# Top.net
KiCad netlist of a schematic drawn in Altium Designer
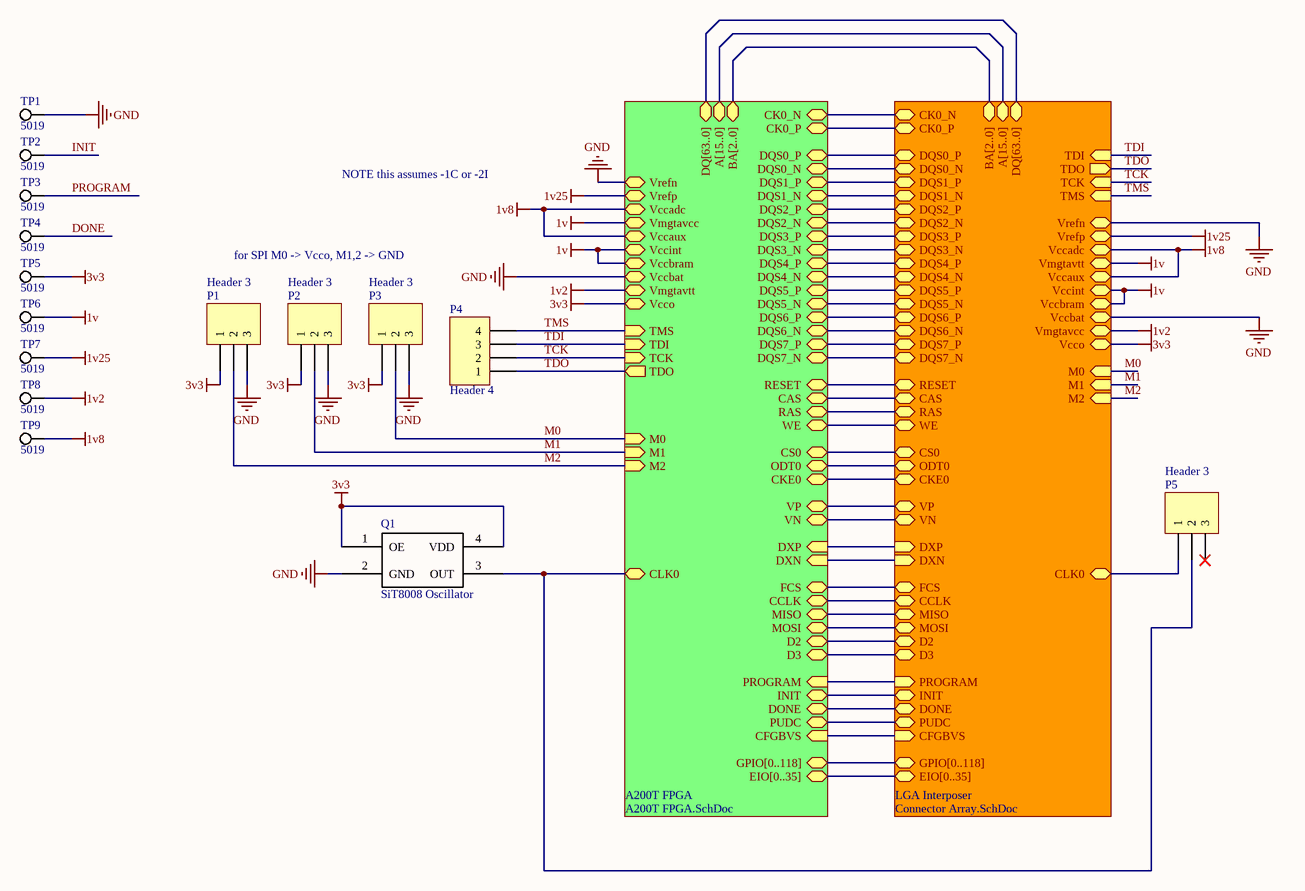
[diagram p0: Top.SchDoc]

(export (version "E")
  (design (tool "Eeschema 10.0.6"))
  (components
    (comp (ref "P1")
      (value "Header 3")
      (footprint "HDR1X3")
      (description "Header, 3-Pin")
      (fields (field (name "PUBLISHER") "Altium Limited"))
      (libsource (lib "Miscellaneous Connectors") (part "Header 3"))
    )
    (comp (ref "P2")
      (value "Header 3")
      (footprint "HDR1X3")
      (description "Header, 3-Pin")
      (fields (field (name "PUBLISHER") "Altium Limited"))
      (libsource (lib "Miscellaneous Connectors") (part "Header 3"))
    )
    (comp (ref "P3")
      (value "Header 3")
      (footprint "HDR1X3")
      (description "Header, 3-Pin")
      (fields (field (name "PUBLISHER") "Altium Limited"))
      (libsource (lib "Miscellaneous Connectors") (part "Header 3"))
    )
    (comp (ref "P4")
      (value "Header 4")
      (footprint "HDR1X4")
      (description "Header, 4-Pin")
      (fields (field (name "PUBLISHER") "Altium Limited"))
      (libsource (lib "Miscellaneous Connectors") (part "Header 4"))
    )
    (comp (ref "P5")
      (value "Header 3")
      (footprint "HDR1X3")
      (description "Header, 3-Pin")
      (fields (field (name "PUBLISHER") "Altium Limited"))
      (libsource (lib "Miscellaneous Connectors") (part "Header 3"))
    )
    (comp (ref "Q1")
      (value "SiT8008 Oscillator")
      (footprint "SiT8008 2.5x2")
      (libsource (lib "2020-09-26_17-27-19") (part "SiT8008 Oscillator"))
    )
    (comp (ref "TP1")
      (value "5019")
      (footprint "KSTN-5019_V")
      (description "Test Point, 1 Position SMD, RoHS, Tape and Reel")
      (libsource (lib "Altium Content Vault") (part "TESTPOINT_WHITE"))
    )
    (comp (ref "TP2")
      (value "5019")
      (footprint "KSTN-5019_V")
      (description "Test Point, 1 Position SMD, RoHS, Tape and Reel")
      (libsource (lib "Altium Content Vault") (part "TESTPOINT_WHITE"))
    )
    (comp (ref "TP3")
      (value "5019")
      (footprint "KSTN-5019_V")
      (description "Test Point, 1 Position SMD, RoHS, Tape and Reel")
      (libsource (lib "Altium Content Vault") (part "TESTPOINT_WHITE"))
    )
    (comp (ref "TP4")
      (value "5019")
      (footprint "KSTN-5019_V")
      (description "Test Point, 1 Position SMD, RoHS, Tape and Reel")
      (libsource (lib "Altium Content Vault") (part "TESTPOINT_WHITE"))
    )
    (comp (ref "TP5")
      (value "5019")
      (footprint "KSTN-5019_V")
      (description "Test Point, 1 Position SMD, RoHS, Tape and Reel")
      (libsource (lib "Altium Content Vault") (part "TESTPOINT_WHITE"))
    )
    (comp (ref "TP6")
      (value "5019")
      (footprint "KSTN-5019_V")
      (description "Test Point, 1 Position SMD, RoHS, Tape and Reel")
      (libsource (lib "Altium Content Vault") (part "TESTPOINT_WHITE"))
    )
    (comp (ref "TP7")
      (value "5019")
      (footprint "KSTN-5019_V")
      (description "Test Point, 1 Position SMD, RoHS, Tape and Reel")
      (libsource (lib "Altium Content Vault") (part "TESTPOINT_WHITE"))
    )
    (comp (ref "TP8")
      (value "5019")
      (footprint "KSTN-5019_V")
      (description "Test Point, 1 Position SMD, RoHS, Tape and Reel")
      (libsource (lib "Altium Content Vault") (part "TESTPOINT_WHITE"))
    )
    (comp (ref "TP9")
      (value "5019")
      (footprint "KSTN-5019_V")
      (description "Test Point, 1 Position SMD, RoHS, Tape and Reel")
      (libsource (lib "Altium Content Vault") (part "TESTPOINT_WHITE"))
    )
  )
  (nets
    (net (code "9") (name "/CLK0") (class "Default")
      (node (ref "P5") (pin "1") (pinfunction "1_1") (pintype "passive"))
    )
    (net (code "10") (name "/CLK0_1") (class "Default")
      (node (ref "P5") (pin "2") (pinfunction "2_2") (pintype "passive"))
      (node (ref "Q1") (pin "3") (pinfunction "OUT_3") (pintype "passive"))
    )
    (net (code "14") (name "/DONE") (class "Default")
      (node (ref "TP4") (pin "1") (pinfunction "1_1") (pintype "passive"))
    )
    (net (code "38") (name "/INIT") (class "Default")
      (node (ref "TP2") (pin "1") (pinfunction "1_1") (pintype "passive"))
    )
    (net (code "40") (name "/M0") (class "Default")
      (node (ref "P3") (pin "2") (pinfunction "2_2") (pintype "passive"))
    )
    (net (code "41") (name "/M1") (class "Default")
      (node (ref "P2") (pin "2") (pinfunction "2_2") (pintype "passive"))
    )
    (net (code "42") (name "/M2") (class "Default")
      (node (ref "P1") (pin "2") (pinfunction "2_2") (pintype "passive"))
    )
    (net (code "46") (name "/PROGRAM") (class "Default")
      (node (ref "TP3") (pin "1") (pinfunction "1_1") (pintype "passive"))
    )
    (net (code "51") (name "/TCK") (class "Default")
      (node (ref "P4") (pin "2") (pinfunction "2_2") (pintype "passive"))
    )
    (net (code "52") (name "/TDI") (class "Default")
      (node (ref "P4") (pin "3") (pinfunction "3_3") (pintype "passive"))
    )
    (net (code "53") (name "/TDO") (class "Default")
      (node (ref "P4") (pin "1") (pinfunction "1_1") (pintype "passive"))
    )
    (net (code "54") (name "/TMS") (class "Default")
      (node (ref "P4") (pin "4") (pinfunction "4_4") (pintype "passive"))
    )
    (net (code "58") (name "1v") (class "Default")
      (node (ref "TP6") (pin "1") (pinfunction "1_1") (pintype "passive"))
    )
    (net (code "59") (name "1v2") (class "Default")
      (node (ref "TP8") (pin "1") (pinfunction "1_1") (pintype "passive"))
    )
    (net (code "60") (name "1v8") (class "Default")
      (node (ref "TP9") (pin "1") (pinfunction "1_1") (pintype "passive"))
    )
    (net (code "61") (name "1v25") (class "Default")
      (node (ref "TP7") (pin "1") (pinfunction "1_1") (pintype "passive"))
    )
    (net (code "62") (name "3v3") (class "Default")
      (node (ref "P1") (pin "1") (pinfunction "1_1") (pintype "passive"))
      (node (ref "P2") (pin "1") (pinfunction "1_1") (pintype "passive"))
      (node (ref "P3") (pin "1") (pinfunction "1_1") (pintype "passive"))
      (node (ref "Q1") (pin "1") (pinfunction "OE_1") (pintype "passive"))
      (node (ref "Q1") (pin "4") (pinfunction "VDD_4") (pintype "passive"))
      (node (ref "TP5") (pin "1") (pinfunction "1_1") (pintype "passive"))
    )
    (net (code "63") (name "GND") (class "Default")
      (node (ref "P1") (pin "3") (pinfunction "3_3") (pintype "passive"))
      (node (ref "P2") (pin "3") (pinfunction "3_3") (pintype "passive"))
      (node (ref "P3") (pin "3") (pinfunction "3_3") (pintype "passive"))
      (node (ref "Q1") (pin "2") (pinfunction "GND_2") (pintype "passive"))
      (node (ref "TP1") (pin "1") (pinfunction "1_1") (pintype "passive"))
    )
    (net (code "64") (name "unconnected-(P5-Pad3)") (class "Default")
      (node (ref "P5") (pin "3") (pinfunction "3_3") (pintype "passive+no_connect"))
    )
  )
)
